# pwr_ctl.net
KiCad netlist of a schematic drawn in Altium Designer
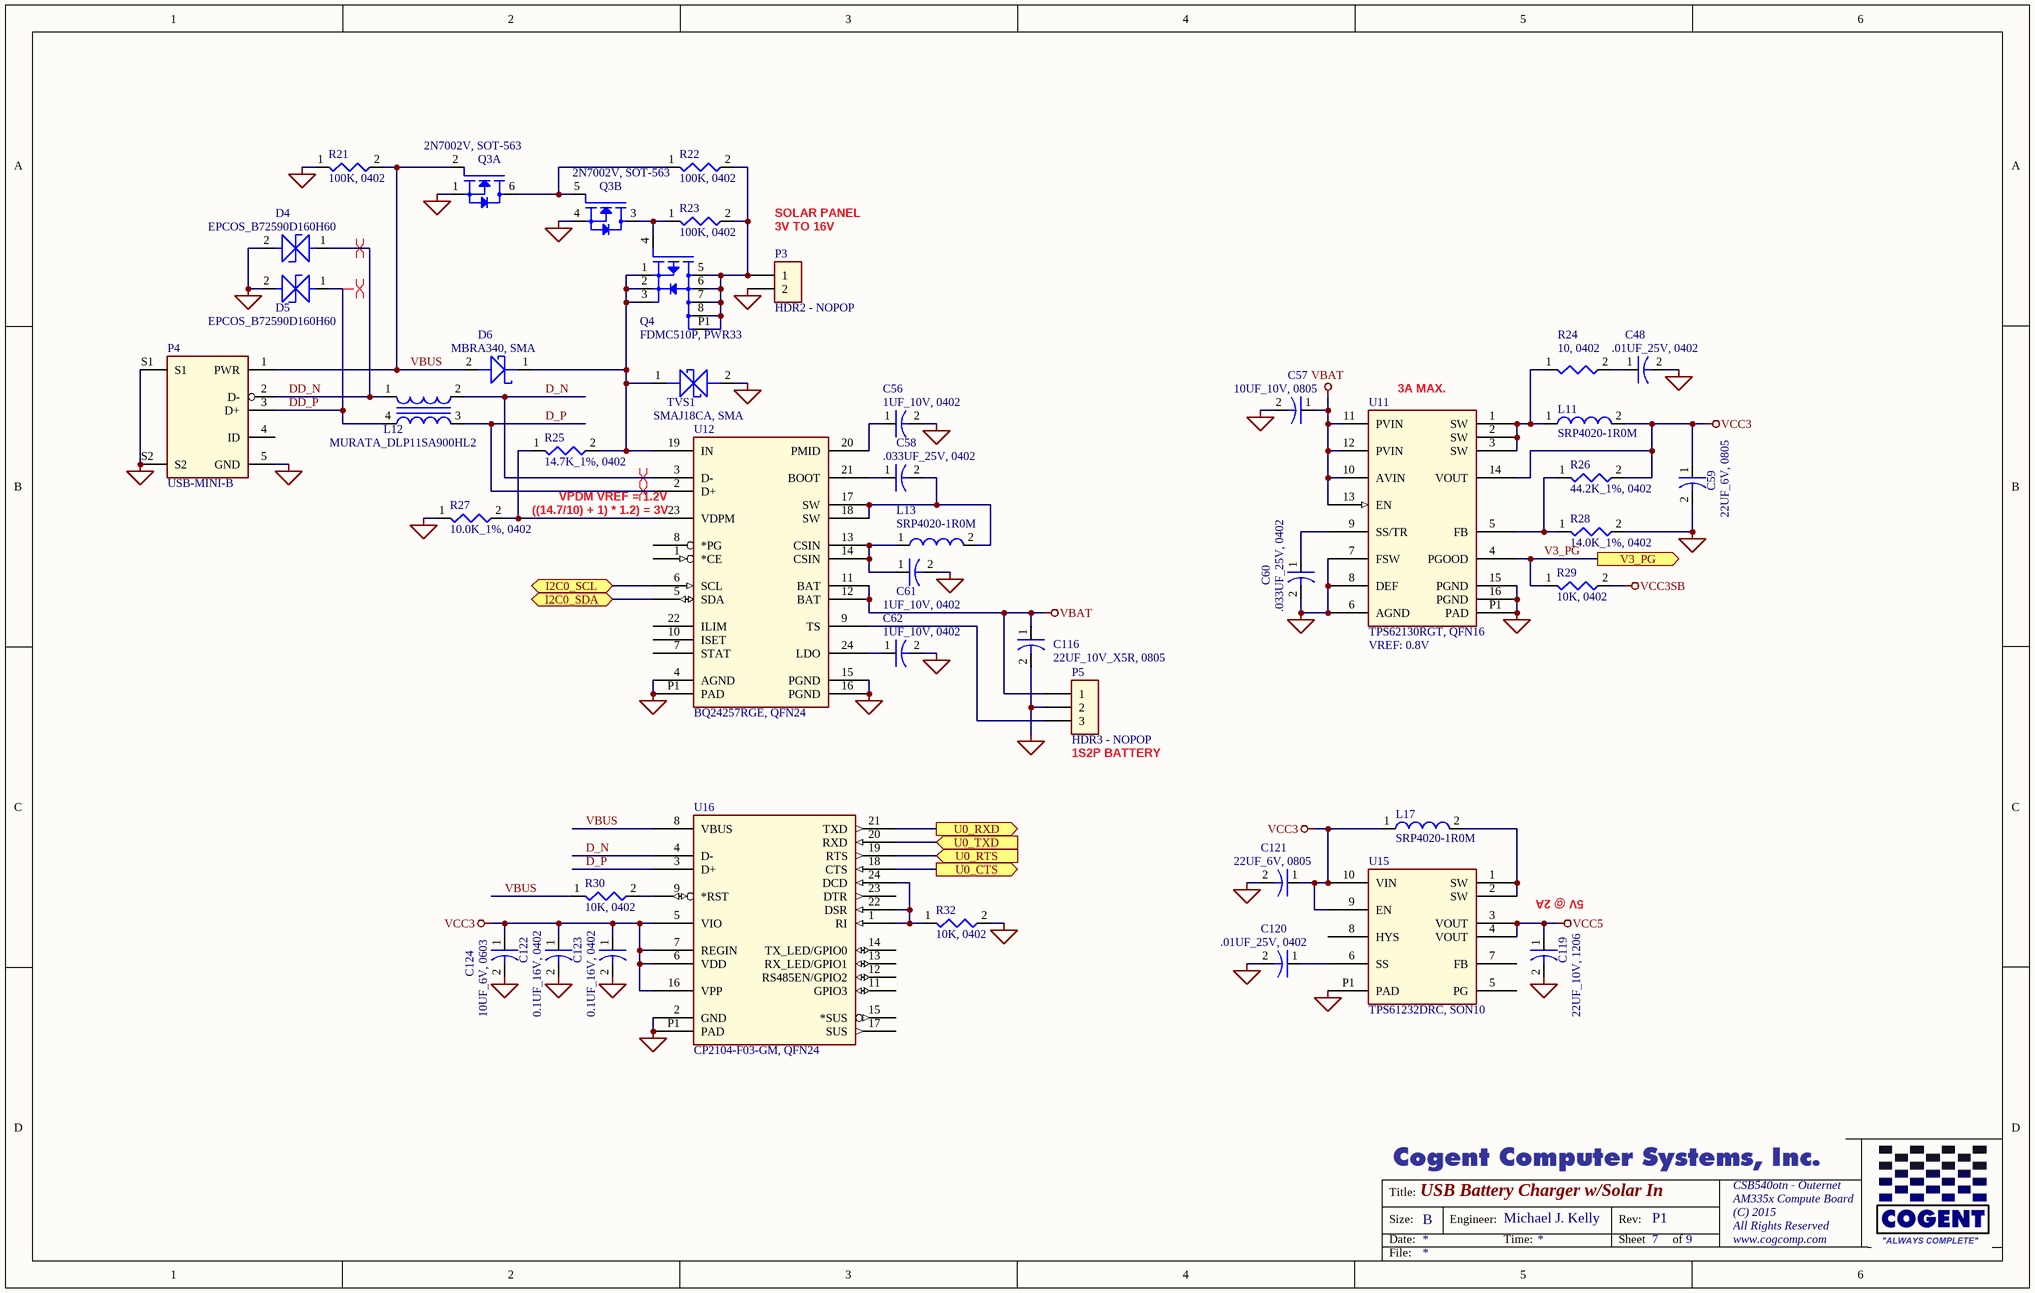
[diagram p0: pwr_ctl.SchDoc]

(export (version "E")
  (design (tool "Eeschema 10.0.6"))
  (components
    (comp (ref "C48")
      (value ".01UF_25V, 0402")
      (footprint "0402C")
      (description "CAP - 0402 PKG")
      (libsource (lib "COGENT_Library") (part ".01UF_25V, 0402"))
    )
    (comp (ref "C56")
      (value "1UF_10V, 0402")
      (footprint "0402C")
      (description "CAP - 0402 PKG")
      (libsource (lib "COGENT_Library") (part "1UF_10V, 0402"))
    )
    (comp (ref "C57")
      (value "10UF_10V, 0805")
      (footprint "0805C")
      (description "CAP - 0805 PKG")
      (libsource (lib "COGENT_Library") (part "10UF_10V, 0805"))
    )
    (comp (ref "C58")
      (value ".033UF_25V, 0402")
      (footprint "0402C")
      (description "CAP - 0402 PKG")
      (libsource (lib "COGENT_Library") (part ".033UF_25V, 0402"))
    )
    (comp (ref "C59")
      (value "22UF_6V, 0805")
      (footprint "0805C")
      (description "CAP - 0805 PKG")
      (libsource (lib "COGENT_Library") (part "22UF_6V, 0805"))
    )
    (comp (ref "C60")
      (value ".033UF_25V, 0402")
      (footprint "0402C")
      (description "CAP - 0402 PKG")
      (libsource (lib "COGENT_Library") (part ".033UF_25V, 0402"))
    )
    (comp (ref "C61")
      (value "1UF_10V, 0402")
      (footprint "0402C")
      (description "CAP - 0402 PKG")
      (libsource (lib "COGENT_Library") (part "1UF_10V, 0402"))
    )
    (comp (ref "C62")
      (value "1UF_10V, 0402")
      (footprint "0402C")
      (description "CAP - 0402 PKG")
      (libsource (lib "COGENT_Library") (part "1UF_10V, 0402"))
    )
    (comp (ref "C116")
      (value "22UF_10V_X5R, 0805")
      (footprint "0805C")
      (description "CAP - 0805 PKG")
      (libsource (lib "COGENT_Library") (part "22UF_10V_X5R, 0805"))
    )
    (comp (ref "C119")
      (value "22UF_10V, 1206")
      (footprint "1206C")
      (description "CAP - 1206 PKG")
      (libsource (lib "COGENT_Library") (part "22UF_10V, 1206"))
    )
    (comp (ref "C120")
      (value ".01UF_25V, 0402")
      (footprint "0402C")
      (description "CAP - 0402 PKG")
      (libsource (lib "COGENT_Library") (part ".01UF_25V, 0402"))
    )
    (comp (ref "C121")
      (value "22UF_6V, 0805")
      (footprint "0805C")
      (description "CAP - 0805 PKG")
      (libsource (lib "COGENT_Library") (part "22UF_6V, 0805"))
    )
    (comp (ref "C122")
      (value "0.1UF_16V, 0402")
      (footprint "0402C")
      (description "CAP - 0402 PKG")
      (libsource (lib "COGENT_Library") (part "0.1UF_16V, 0402"))
    )
    (comp (ref "C123")
      (value "0.1UF_16V, 0402")
      (footprint "0402C")
      (description "CAP - 0402 PKG")
      (libsource (lib "COGENT_Library") (part "0.1UF_16V, 0402"))
    )
    (comp (ref "C124")
      (value "10UF_6V, 0603")
      (footprint "0603C")
      (description "CAP - 0603 PKG")
      (libsource (lib "COGENT_Library") (part "10UF_6V, 0603"))
    )
    (comp (ref "D4")
      (value "EPCOS_B72590D160H60")
      (footprint "0402L")
      (description "DIODE - VARISTOR, 16VDC 2PF 0402")
      (libsource (lib "COGENT_Library") (part "EPCOS_B72590D160H60"))
    )
    (comp (ref "D5")
      (value "EPCOS_B72590D160H60")
      (footprint "0402L")
      (description "DIODE - VARISTOR, 16VDC 2PF 0402")
      (libsource (lib "COGENT_Library") (part "EPCOS_B72590D160H60"))
    )
    (comp (ref "D6")
      (value "MBRA340, SMA")
      (footprint "SMA")
      (description "DIODE - POWER, SCHOTTKY, 40V, 3A")
      (libsource (lib "COGENT_Library") (part "MBRA340, SMA"))
    )
    (comp (ref "L11")
      (value "SRP4020-1R0M")
      (footprint "SRP4020")
      (description "INDUCTOR - 1.0UH, 5/6A, 4MM x 4MM x 2MM, 22mohm")
      (libsource (lib "COGENT_Library") (part "SRP4020-1R0M"))
    )
    (comp (ref "L12")
      (value "MURATA_DLP11SA900HL2")
      (footprint "PANASONIC_EXC24C")
      (description "FERRITE - COMMON MODE FILTER, USB2/HDMI/GIGe, FILM")
      (libsource (lib "COGENT_Library") (part "MURATA_DLP11SA900HL2"))
    )
    (comp (ref "L13")
      (value "SRP4020-1R0M")
      (footprint "SRP4020")
      (description "INDUCTOR - 1.0UH, 5/6A, 4MM x 4MM x 2MM, 22mohm")
      (libsource (lib "COGENT_Library") (part "SRP4020-1R0M"))
    )
    (comp (ref "L17")
      (value "SRP4020-1R0M")
      (footprint "SRP4020")
      (description "INDUCTOR - 1.0UH, 5/6A, 4MM x 4MM x 2MM, 22mohm")
      (libsource (lib "COGENT_Library") (part "SRP4020-1R0M"))
    )
    (comp (ref "P3")
      (value "HDR2 - NOPOP")
      (footprint "HDR2X1-NOPOP")
      (description "HEADER - 2-PIN, HOLES ONLY FOR WIRE")
      (libsource (lib "COGENT_Library") (part "HDR2 - NOPOP"))
    )
    (comp (ref "P4")
      (value "USB-MINI-B")
      (footprint "USB-MINI-B")
      (description "CONN - USB TYPE B MINI")
      (libsource (lib "COGENT_Library") (part "USB-MINI-B"))
    )
    (comp (ref "P5")
      (value "HDR3 - NOPOP")
      (footprint "HDR3X1-NOPOP")
      (description "HEADER - 3-PIN, HOLES ONLY FOR WIRE")
      (libsource (lib "COGENT_Library") (part "HDR3 - NOPOP"))
    )
    (comp (ref "Q3")
      (value "2N7002V, SOT-563")
      (footprint "SOT-563")
      (description "N-FET - DUAL, 60V, 500ma @ 10V, Vgs(th) 2V")
      (libsource (lib "COGENT_Library") (part "2N7002V, SOT-563"))
    )
    (comp (ref "Q4")
      (value "FDMC510P, PWR33")
      (footprint "POWER-33")
      (description "P-FET - 20V, 8.3A @ 1.5Vgs, 17mohm")
      (libsource (lib "COGENT_Library") (part "FDMC510P, PWR33"))
    )
    (comp (ref "R21")
      (value "100K, 0402")
      (footprint "0402R")
      (description "RES - 0402 PKG")
      (libsource (lib "COGENT_Library") (part "100K, 0402"))
    )
    (comp (ref "R22")
      (value "100K, 0402")
      (footprint "0402R")
      (description "RES - 0402 PKG")
      (libsource (lib "COGENT_Library") (part "100K, 0402"))
    )
    (comp (ref "R23")
      (value "100K, 0402")
      (footprint "0402R")
      (description "RES - 0402 PKG")
      (libsource (lib "COGENT_Library") (part "100K, 0402"))
    )
    (comp (ref "R24")
      (value "10, 0402")
      (footprint "0402R")
      (description "RES - 0402 PKG")
      (libsource (lib "COGENT_Library") (part "10, 0402"))
    )
    (comp (ref "R25")
      (value "14.7K_1%, 0402")
      (footprint "0402R")
      (description "RES - 0402 PKG")
      (libsource (lib "COGENT_Library") (part "14.7K_1%, 0402"))
    )
    (comp (ref "R26")
      (value "44.2K_1%, 0402")
      (footprint "0402R")
      (description "RES - 0402 PKG")
      (libsource (lib "COGENT_Library") (part "44.2K_1%, 0402"))
    )
    (comp (ref "R27")
      (value "10.0K_1%, 0402")
      (footprint "0402R")
      (description "RES - 0402 PKG")
      (libsource (lib "COGENT_Library") (part "10.0K_1%, 0402"))
    )
    (comp (ref "R28")
      (value "14.0K_1%, 0402")
      (footprint "0402R")
      (description "RES - 0402 PKG")
      (libsource (lib "COGENT_Library") (part "14.0K_1%, 0402"))
    )
    (comp (ref "R29")
      (value "10K, 0402")
      (footprint "0402R")
      (description "RES - 0402 PKG")
      (libsource (lib "COGENT_Library") (part "10K, 0402"))
    )
    (comp (ref "R30")
      (value "10K, 0402")
      (footprint "0402R")
      (description "RES - 0402 PKG")
      (libsource (lib "COGENT_Library") (part "10K, 0402"))
    )
    (comp (ref "R32")
      (value "10K, 0402")
      (footprint "0402R")
      (description "RES - 0402 PKG")
      (libsource (lib "COGENT_Library") (part "10K, 0402"))
    )
    (comp (ref "TVS1")
      (value "SMAJ18CA, SMA")
      (footprint "SMA")
      (description "DIODE - TVS, 20V MIN., 22.1V MAX.")
      (libsource (lib "COGENT_Library") (part "SMAJ18CA, SMA"))
    )
    (comp (ref "U11")
      (value "TPS62130RGT, QFN16")
      (footprint "QFN16-3MM")
      (description "SWITCHER - 17ua Iq, 3A, 3V TO 17V IN, 0.9V TO 6V OUT")
      (fields (field (name "VREF") "0.8V"))
      (libsource (lib "COGENT_Library") (part "TPS62130RGT, QFN16"))
    )
    (comp (ref "U12")
      (value "BQ24257RGE, QFN24")
      (footprint "QFN24")
      (description "IC - BATTERY CHARGER USB BC1.2, 1CELL, 2A")
      (libsource (lib "COGENT_Library") (part "BQ24257RGE, QFN24"))
    )
    (comp (ref "U15")
      (value "TPS61232DRC, SON10")
      (footprint "SON10")
      (description "SWITCHER - 500ua Iq, BOOST 5A, 2.3V TO 5.5V IN, 2.5V TO 5.5V OUT")
      (libsource (lib "COGENT_Library") (part "TPS61232DRC, SON10"))
    )
    (comp (ref "U16")
      (value "CP2104-F03-GM, QFN24")
      (footprint "QFN24")
      (description "USB - UART W/4 GPIO")
      (libsource (lib "COGENT_Library") (part "CP2104-F03-GM, QFN24"))
    )
  )
  (nets
    (net (code "1") (name "/DD_N") (class "Default")
      (node (ref "D4") (pin "1") (pinfunction "ANODE_1") (pintype "passive"))
      (node (ref "L12") (pin "1") (pinfunction "1_1") (pintype "passive"))
      (node (ref "P4") (pin "2") (pinfunction "D-_2") (pintype "passive"))
    )
    (net (code "2") (name "/DD_P") (class "Default")
      (node (ref "D5") (pin "1") (pinfunction "ANODE_1") (pintype "passive"))
      (node (ref "L12") (pin "4") (pinfunction "4_4") (pintype "passive"))
      (node (ref "P4") (pin "3") (pinfunction "D+_3") (pintype "passive"))
    )
    (net (code "3") (name "/D_N") (class "Default")
      (node (ref "L12") (pin "2") (pinfunction "2_2") (pintype "passive"))
      (node (ref "U12") (pin "3") (pinfunction "D-_3") (pintype "passive"))
      (node (ref "U16") (pin "4") (pinfunction "D-_4") (pintype "passive"))
    )
    (net (code "4") (name "/D_P") (class "Default")
      (node (ref "L12") (pin "3") (pinfunction "3_3") (pintype "passive"))
      (node (ref "U12") (pin "2") (pinfunction "D+_2") (pintype "passive"))
      (node (ref "U16") (pin "3") (pinfunction "D+_3") (pintype "passive"))
    )
    (net (code "5") (name "/I2C0_SCL") (class "Default")
      (node (ref "U12") (pin "6") (pinfunction "SCL_6") (pintype "input"))
    )
    (net (code "6") (name "/I2C0_SDA") (class "Default")
      (node (ref "U12") (pin "5") (pinfunction "SDA_5") (pintype "bidirectional"))
    )
    (net (code "7") (name "/U0_CTS") (class "Default")
      (node (ref "U16") (pin "18") (pinfunction "CTS_18") (pintype "input"))
    )
    (net (code "8") (name "/U0_RTS") (class "Default")
      (node (ref "U16") (pin "19") (pinfunction "RTS_19") (pintype "output"))
    )
    (net (code "9") (name "/U0_RXD") (class "Default")
      (node (ref "U16") (pin "21") (pinfunction "TXD_21") (pintype "output"))
    )
    (net (code "10") (name "/U0_TXD") (class "Default")
      (node (ref "U16") (pin "20") (pinfunction "RXD_20") (pintype "input"))
    )
    (net (code "11") (name "/V3_PG") (class "Default")
      (node (ref "R29") (pin "1") (pinfunction "1_1") (pintype "passive"))
      (node (ref "U11") (pin "4") (pinfunction "PGOOD_4") (pintype "open_collector"))
    )
    (net (code "12") (name "/VBUS") (class "Default")
      (node (ref "D6") (pin "2") (pinfunction "ANODE_2") (pintype "passive"))
      (node (ref "P4") (pin "1") (pinfunction "PWR_1") (pintype "power_in"))
      (node (ref "Q3") (pin "2") (pinfunction "2_2") (pintype "passive"))
      (node (ref "R21") (pin "2") (pinfunction "2_2") (pintype "passive"))
      (node (ref "R30") (pin "1") (pinfunction "1_1") (pintype "passive"))
      (node (ref "U16") (pin "8") (pinfunction "VBUS_8") (pintype "passive"))
    )
    (net (code "13") (name "GND") (class "Default")
      (node (ref "C116") (pin "2") (pinfunction "2_2") (pintype "passive"))
      (node (ref "C119") (pin "2") (pinfunction "2_2") (pintype "passive"))
      (node (ref "C120") (pin "2") (pinfunction "2_2") (pintype "passive"))
      (node (ref "C121") (pin "2") (pinfunction "2_2") (pintype "passive"))
      (node (ref "C122") (pin "2") (pinfunction "2_2") (pintype "passive"))
      (node (ref "C123") (pin "2") (pinfunction "2_2") (pintype "passive"))
      (node (ref "C124") (pin "2") (pinfunction "2_2") (pintype "passive"))
      (node (ref "C48") (pin "2") (pinfunction "2_2") (pintype "passive"))
      (node (ref "C56") (pin "2") (pinfunction "2_2") (pintype "passive"))
      (node (ref "C57") (pin "2") (pinfunction "2_2") (pintype "passive"))
      (node (ref "C59") (pin "2") (pinfunction "2_2") (pintype "passive"))
      (node (ref "C60") (pin "2") (pinfunction "2_2") (pintype "passive"))
      (node (ref "C61") (pin "2") (pinfunction "2_2") (pintype "passive"))
      (node (ref "C62") (pin "2") (pinfunction "2_2") (pintype "passive"))
      (node (ref "D4") (pin "2") (pinfunction "CATHODE_2") (pintype "passive"))
      (node (ref "D5") (pin "2") (pinfunction "CATHODE_2") (pintype "passive"))
      (node (ref "P3") (pin "2") (pinfunction "2_2") (pintype "passive"))
      (node (ref "P4") (pin "5") (pinfunction "GND_5") (pintype "power_in"))
      (node (ref "P4") (pin "S1") (pinfunction "S1_S1") (pintype "passive"))
      (node (ref "P4") (pin "S2") (pinfunction "S2_S2") (pintype "passive"))
      (node (ref "P5") (pin "2") (pinfunction "2_2") (pintype "passive"))
      (node (ref "Q3") (pin "1") (pinfunction "1_1") (pintype "passive"))
      (node (ref "Q3") (pin "4") (pinfunction "1_4") (pintype "passive"))
      (node (ref "R21") (pin "1") (pinfunction "1_1") (pintype "passive"))
      (node (ref "R27") (pin "1") (pinfunction "1_1") (pintype "passive"))
      (node (ref "R28") (pin "2") (pinfunction "2_2") (pintype "passive"))
      (node (ref "R32") (pin "2") (pinfunction "2_2") (pintype "passive"))
      (node (ref "TVS1") (pin "2") (pinfunction "2_2") (pintype "passive"))
      (node (ref "U11") (pin "15") (pinfunction "PGND_15") (pintype "power_in"))
      (node (ref "U11") (pin "16") (pinfunction "PGND_16") (pintype "power_in"))
      (node (ref "U11") (pin "6") (pinfunction "AGND_6") (pintype "power_in"))
      (node (ref "U11") (pin "7") (pinfunction "FSW_7") (pintype "passive"))
      (node (ref "U11") (pin "8") (pinfunction "DEF_8") (pintype "passive"))
      (node (ref "U11") (pin "P1") (pinfunction "PAD_P1") (pintype "power_in"))
      (node (ref "U12") (pin "15") (pinfunction "PGND_15") (pintype "passive"))
      (node (ref "U12") (pin "16") (pinfunction "PGND_16") (pintype "passive"))
      (node (ref "U12") (pin "4") (pinfunction "AGND_4") (pintype "passive"))
      (node (ref "U12") (pin "P1") (pinfunction "PAD_P1") (pintype "passive"))
      (node (ref "U15") (pin "P1") (pinfunction "PAD_P1") (pintype "power_in"))
      (node (ref "U16") (pin "2") (pinfunction "GND_2") (pintype "power_in"))
      (node (ref "U16") (pin "P1") (pinfunction "PAD_P1") (pintype "passive"))
    )
    (net (code "14") (name "Net-(C48-Pad1)") (class "Default")
      (node (ref "C48") (pin "1") (pinfunction "1_1") (pintype "passive"))
      (node (ref "R24") (pin "2") (pinfunction "2_2") (pintype "passive"))
    )
    (net (code "15") (name "Net-(C58-Pad2)") (class "Default")
      (node (ref "C58") (pin "2") (pinfunction "2_2") (pintype "passive"))
      (node (ref "L13") (pin "2") (pinfunction "2_2") (pintype "passive"))
      (node (ref "U12") (pin "17") (pinfunction "SW_17") (pintype "passive"))
      (node (ref "U12") (pin "18") (pinfunction "SW_18") (pintype "passive"))
    )
    (net (code "16") (name "Net-(C61-Pad1)") (class "Default")
      (node (ref "C61") (pin "1") (pinfunction "1_1") (pintype "passive"))
      (node (ref "L13") (pin "1") (pinfunction "1_1") (pintype "passive"))
      (node (ref "U12") (pin "13") (pinfunction "CSIN_13") (pintype "passive"))
      (node (ref "U12") (pin "14") (pinfunction "CSIN_14") (pintype "passive"))
    )
    (net (code "17") (name "Net-(D6-CATHODE)") (class "Default")
      (node (ref "D6") (pin "1") (pinfunction "CATHODE_1") (pintype "passive"))
      (node (ref "Q4") (pin "1") (pinfunction "1_1") (pintype "passive"))
      (node (ref "Q4") (pin "2") (pinfunction "2_2") (pintype "passive"))
      (node (ref "Q4") (pin "3") (pinfunction "3_3") (pintype "passive"))
      (node (ref "R25") (pin "2") (pinfunction "2_2") (pintype "passive"))
      (node (ref "TVS1") (pin "1") (pinfunction "1_1") (pintype "passive"))
      (node (ref "U12") (pin "19") (pinfunction "IN_19") (pintype "passive"))
    )
    (net (code "18") (name "Net-(L11-Pad1)") (class "Default")
      (node (ref "L11") (pin "1") (pinfunction "1_1") (pintype "passive"))
      (node (ref "R24") (pin "1") (pinfunction "1_1") (pintype "passive"))
      (node (ref "U11") (pin "1") (pinfunction "SW_1") (pintype "passive"))
      (node (ref "U11") (pin "2") (pinfunction "SW_2") (pintype "passive"))
      (node (ref "U11") (pin "3") (pinfunction "SW_3") (pintype "passive"))
    )
    (net (code "19") (name "Net-(L17-Pad2)") (class "Default")
      (node (ref "L17") (pin "2") (pinfunction "2_2") (pintype "passive"))
      (node (ref "U15") (pin "1") (pinfunction "SW_1") (pintype "open_collector"))
      (node (ref "U15") (pin "2") (pinfunction "SW_2") (pintype "passive"))
    )
    (net (code "20") (name "Net-(Q3B-2)") (class "Default")
      (node (ref "Q3") (pin "5") (pinfunction "2_5") (pintype "passive"))
      (node (ref "Q3") (pin "6") (pinfunction "6_6") (pintype "passive"))
      (node (ref "R22") (pin "1") (pinfunction "1_1") (pintype "passive"))
    )
    (net (code "21") (name "Net-(Q3B-6)") (class "Default")
      (node (ref "Q3") (pin "3") (pinfunction "6_3") (pintype "passive"))
      (node (ref "Q4") (pin "4") (pinfunction "4_4") (pintype "passive"))
      (node (ref "R23") (pin "1") (pinfunction "1_1") (pintype "passive"))
    )
    (net (code "22") (name "Net-(Q4-PAD)") (class "Default")
      (node (ref "P3") (pin "1") (pinfunction "1_1") (pintype "passive"))
      (node (ref "Q4") (pin "5") (pinfunction "5_5") (pintype "passive"))
      (node (ref "Q4") (pin "6") (pinfunction "6_6") (pintype "passive"))
      (node (ref "Q4") (pin "7") (pinfunction "7_7") (pintype "passive"))
      (node (ref "Q4") (pin "8") (pinfunction "8_8") (pintype "passive"))
      (node (ref "Q4") (pin "P1") (pinfunction "PAD_P1") (pintype "passive"))
      (node (ref "R22") (pin "2") (pinfunction "2_2") (pintype "passive"))
      (node (ref "R23") (pin "2") (pinfunction "2_2") (pintype "passive"))
    )
    (net (code "23") (name "Net-(U11-FB)") (class "Default")
      (node (ref "R26") (pin "1") (pinfunction "1_1") (pintype "passive"))
      (node (ref "R28") (pin "1") (pinfunction "1_1") (pintype "passive"))
      (node (ref "U11") (pin "5") (pinfunction "FB_5") (pintype "passive"))
    )
    (net (code "24") (name "Net-(U11-SS{slash}TR)") (class "Default")
      (node (ref "C60") (pin "1") (pinfunction "1_1") (pintype "passive"))
      (node (ref "U11") (pin "9") (pinfunction "SS/TR_9") (pintype "passive"))
    )
    (net (code "25") (name "Net-(U12-BOOT)") (class "Default")
      (node (ref "C58") (pin "1") (pinfunction "1_1") (pintype "passive"))
      (node (ref "U12") (pin "21") (pinfunction "BOOT_21") (pintype "passive"))
    )
    (net (code "26") (name "Net-(U12-LDO)") (class "Default")
      (node (ref "C62") (pin "1") (pinfunction "1_1") (pintype "passive"))
      (node (ref "U12") (pin "24") (pinfunction "LDO_24") (pintype "passive"))
    )
    (net (code "27") (name "Net-(U12-PMID)") (class "Default")
      (node (ref "C56") (pin "1") (pinfunction "1_1") (pintype "passive"))
      (node (ref "U12") (pin "20") (pinfunction "PMID_20") (pintype "passive"))
    )
    (net (code "28") (name "Net-(U12-TS)") (class "Default")
      (node (ref "P5") (pin "3") (pinfunction "3_3") (pintype "passive"))
      (node (ref "U12") (pin "9") (pinfunction "TS_9") (pintype "passive"))
    )
    (net (code "29") (name "Net-(U12-VDPM)") (class "Default")
      (node (ref "R25") (pin "1") (pinfunction "1_1") (pintype "passive"))
      (node (ref "R27") (pin "2") (pinfunction "2_2") (pintype "passive"))
      (node (ref "U12") (pin "23") (pinfunction "VDPM_23") (pintype "passive"))
    )
    (net (code "30") (name "Net-(U15-SS)") (class "Default")
      (node (ref "C120") (pin "1") (pinfunction "1_1") (pintype "passive"))
      (node (ref "U15") (pin "6") (pinfunction "SS_6") (pintype "passive"))
    )
    (net (code "31") (name "Net-(U16-*RST)") (class "Default")
      (node (ref "R30") (pin "2") (pinfunction "2_2") (pintype "passive"))
      (node (ref "U16") (pin "9") (pinfunction "*RST_9") (pintype "bidirectional"))
    )
    (net (code "32") (name "Net-(U16-DCD)") (class "Default")
      (node (ref "R32") (pin "1") (pinfunction "1_1") (pintype "passive"))
      (node (ref "U16") (pin "1") (pinfunction "RI_1") (pintype "input"))
      (node (ref "U16") (pin "22") (pinfunction "DSR_22") (pintype "input"))
      (node (ref "U16") (pin "24") (pinfunction "DCD_24") (pintype "input"))
    )
    (net (code "33") (name "VBAT") (class "Default")
      (node (ref "C116") (pin "1") (pinfunction "1_1") (pintype "passive"))
      (node (ref "C57") (pin "1") (pinfunction "1_1") (pintype "passive"))
      (node (ref "P5") (pin "1") (pinfunction "1_1") (pintype "passive"))
      (node (ref "U11") (pin "10") (pinfunction "AVIN_10") (pintype "power_in"))
      (node (ref "U11") (pin "11") (pinfunction "PVIN_11") (pintype "power_in"))
      (node (ref "U11") (pin "12") (pinfunction "PVIN_12") (pintype "power_in"))
      (node (ref "U11") (pin "13") (pinfunction "EN_13") (pintype "input"))
      (node (ref "U12") (pin "11") (pinfunction "BAT_11") (pintype "passive"))
      (node (ref "U12") (pin "12") (pinfunction "BAT_12") (pintype "passive"))
    )
    (net (code "34") (name "VCC3") (class "Default")
      (node (ref "C121") (pin "1") (pinfunction "1_1") (pintype "passive"))
      (node (ref "C122") (pin "1") (pinfunction "1_1") (pintype "passive"))
      (node (ref "C123") (pin "1") (pinfunction "1_1") (pintype "passive"))
      (node (ref "C124") (pin "1") (pinfunction "1_1") (pintype "passive"))
      (node (ref "C59") (pin "1") (pinfunction "1_1") (pintype "passive"))
      (node (ref "L11") (pin "2") (pinfunction "2_2") (pintype "passive"))
      (node (ref "L17") (pin "1") (pinfunction "1_1") (pintype "passive"))
      (node (ref "R26") (pin "2") (pinfunction "2_2") (pintype "passive"))
      (node (ref "U11") (pin "14") (pinfunction "VOUT_14") (pintype "passive"))
      (node (ref "U15") (pin "10") (pinfunction "VIN_10") (pintype "passive"))
      (node (ref "U15") (pin "9") (pinfunction "EN_9") (pintype "passive"))
      (node (ref "U16") (pin "16") (pinfunction "VPP_16") (pintype "power_in"))
      (node (ref "U16") (pin "5") (pinfunction "VIO_5") (pintype "power_in"))
      (node (ref "U16") (pin "6") (pinfunction "VDD_6") (pintype "power_in"))
      (node (ref "U16") (pin "7") (pinfunction "REGIN_7") (pintype "power_in"))
    )
    (net (code "35") (name "VCC3SB") (class "Default")
      (node (ref "R29") (pin "2") (pinfunction "2_2") (pintype "passive"))
    )
    (net (code "36") (name "VCC5") (class "Default")
      (node (ref "C119") (pin "1") (pinfunction "1_1") (pintype "passive"))
      (node (ref "U15") (pin "3") (pinfunction "VOUT_3") (pintype "passive"))
      (node (ref "U15") (pin "4") (pinfunction "VOUT_4") (pintype "passive"))
    )
    (net (code "37") (name "unconnected-(P4-ID-Pad4)") (class "Default")
      (node (ref "P4") (pin "4") (pinfunction "ID_4") (pintype "passive"))
    )
    (net (code "38") (name "unconnected-(U12-*CE-Pad1)") (class "Default")
      (node (ref "U12") (pin "1") (pinfunction "*CE_1") (pintype "input"))
    )
    (net (code "39") (name "unconnected-(U12-*PG-Pad8)") (class "Default")
      (node (ref "U12") (pin "8") (pinfunction "*PG_8") (pintype "open_collector"))
    )
    (net (code "40") (name "unconnected-(U12-ILIM-Pad22)") (class "Default")
      (node (ref "U12") (pin "22") (pinfunction "ILIM_22") (pintype "passive"))
    )
    (net (code "41") (name "unconnected-(U12-ISET-Pad10)") (class "Default")
      (node (ref "U12") (pin "10") (pinfunction "ISET_10") (pintype "passive"))
    )
    (net (code "42") (name "unconnected-(U12-STAT-Pad7)") (class "Default")
      (node (ref "U12") (pin "7") (pinfunction "STAT_7") (pintype "passive"))
    )
    (net (code "43") (name "unconnected-(U15-FB-Pad7)") (class "Default")
      (node (ref "U15") (pin "7") (pinfunction "FB_7") (pintype "power_in"))
    )
    (net (code "44") (name "unconnected-(U15-HYS-Pad8)") (class "Default")
      (node (ref "U15") (pin "8") (pinfunction "HYS_8") (pintype "passive"))
    )
    (net (code "45") (name "unconnected-(U15-PG-Pad5)") (class "Default")
      (node (ref "U15") (pin "5") (pinfunction "PG_5") (pintype "passive"))
    )
    (net (code "46") (name "unconnected-(U16-*SUS-Pad15)") (class "Default")
      (node (ref "U16") (pin "15") (pinfunction "*SUS_15") (pintype "output"))
    )
    (net (code "47") (name "unconnected-(U16-DTR-Pad23)") (class "Default")
      (node (ref "U16") (pin "23") (pinfunction "DTR_23") (pintype "output"))
    )
    (net (code "48") (name "unconnected-(U16-GPIO3-Pad11)") (class "Default")
      (node (ref "U16") (pin "11") (pinfunction "GPIO3_11") (pintype "bidirectional"))
    )
    (net (code "49") (name "unconnected-(U16-RS485EN{slash}GPIO2-Pad12)") (class "Default")
      (node (ref "U16") (pin "12") (pinfunction "RS485EN/GPIO2_12") (pintype "bidirectional"))
    )
    (net (code "50") (name "unconnected-(U16-RX_LED{slash}GPIO1-Pad13)") (class "Default")
      (node (ref "U16") (pin "13") (pinfunction "RX_LED/GPIO1_13") (pintype "bidirectional"))
    )
    (net (code "51") (name "unconnected-(U16-SUS-Pad17)") (class "Default")
      (node (ref "U16") (pin "17") (pinfunction "SUS_17") (pintype "output"))
    )
    (net (code "52") (name "unconnected-(U16-TX_LED{slash}GPIO0-Pad14)") (class "Default")
      (node (ref "U16") (pin "14") (pinfunction "TX_LED/GPIO0_14") (pintype "bidirectional"))
    )
  )
)
